# OakyWing-v0_1.net
KiCad netlist of a schematic drawn in EAGLE
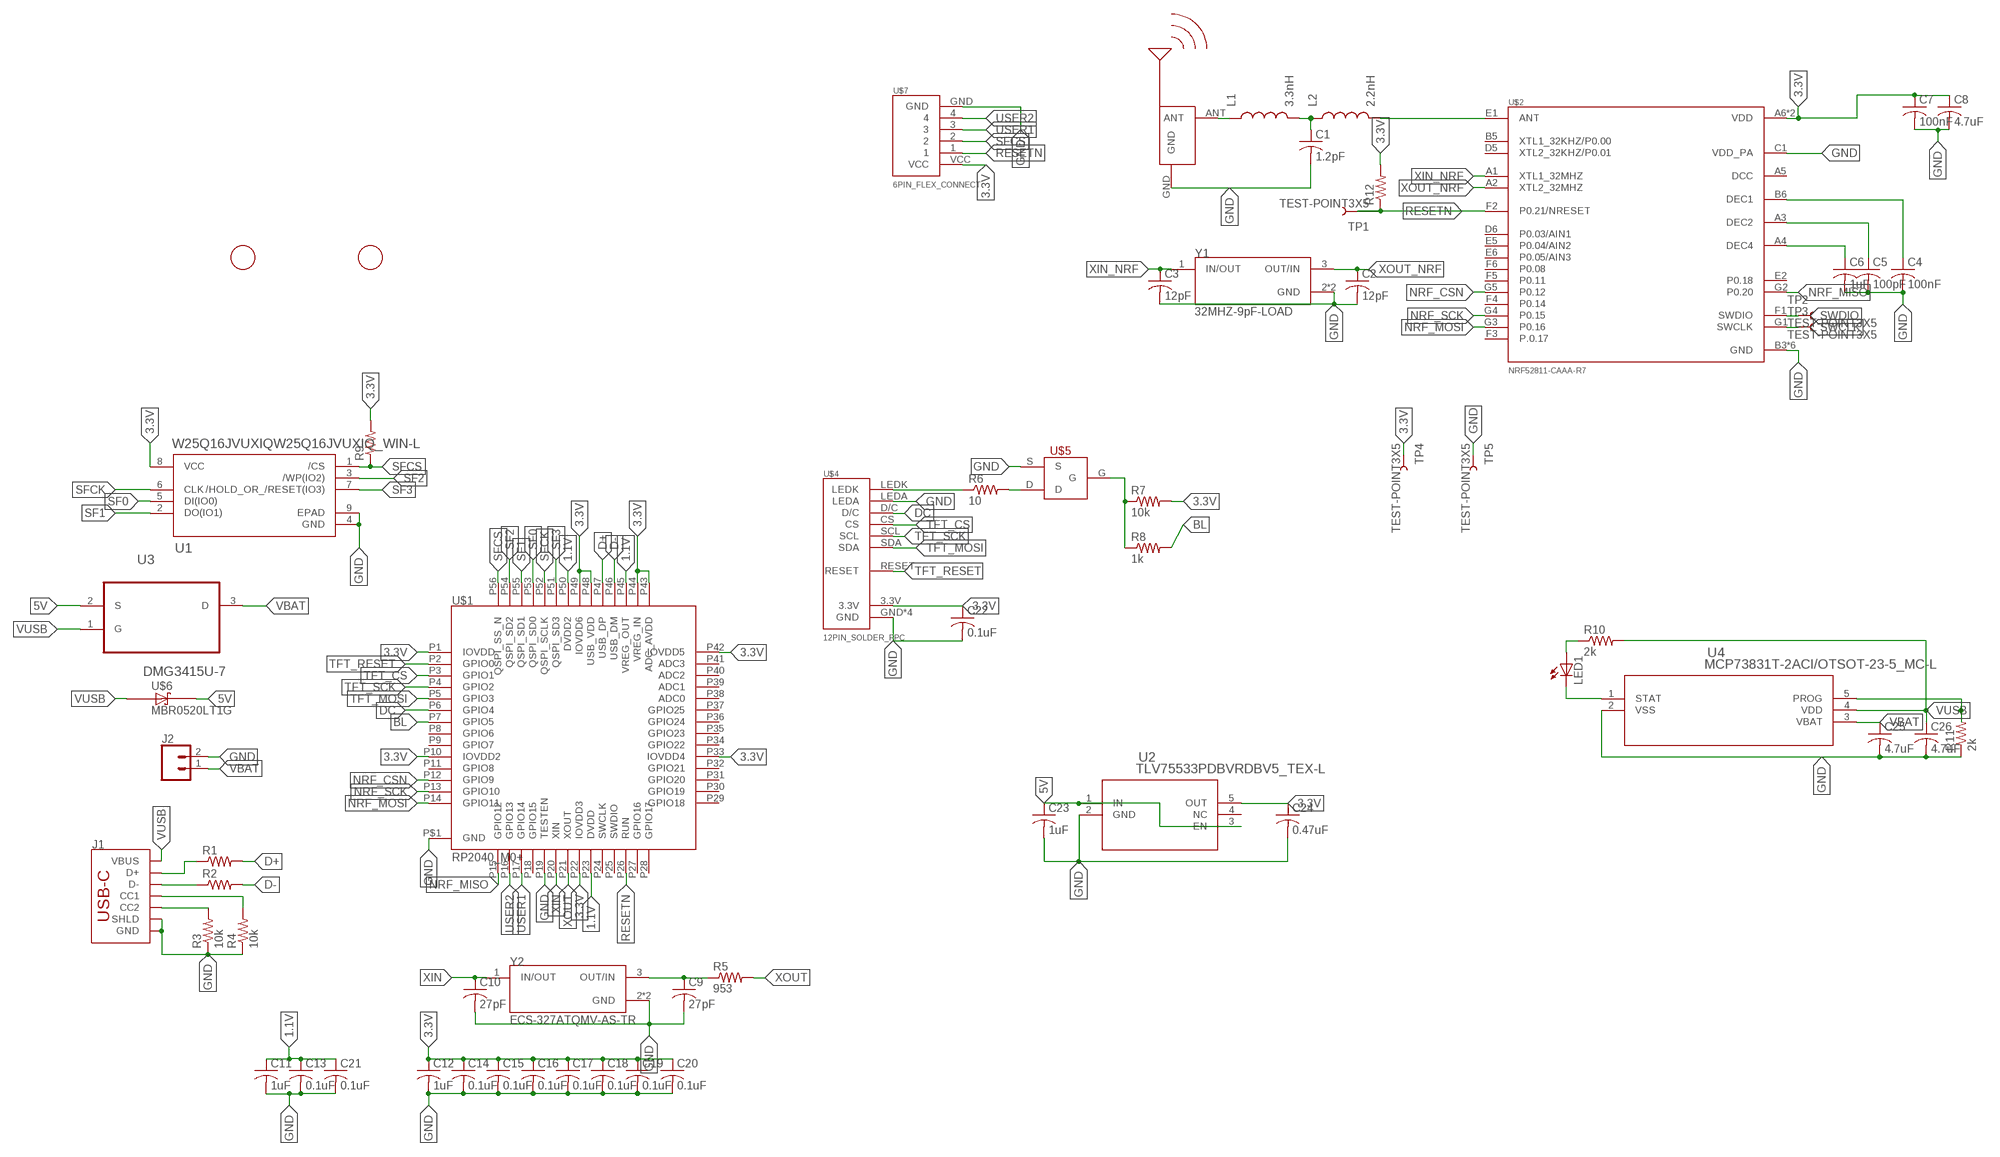
[diagram p0: schematic, sheet 1]

(export (version "E")
  (design (tool "Eeschema 10.0.6"))
  (components
    (comp (ref "C1")
      (value "1.2pF")
      (footprint "eagle-import:C0402")
      (libsource (lib "eagle-import") (part "rcl_334_C-USC0402"))
    )
    (comp (ref "C2")
      (value "12pF")
      (footprint "eagle-import:C0402")
      (libsource (lib "eagle-import") (part "rcl_334_C-USC0402"))
    )
    (comp (ref "C3")
      (value "12pF")
      (footprint "eagle-import:C0402")
      (libsource (lib "eagle-import") (part "C-USC0402"))
    )
    (comp (ref "C4")
      (value "100nF")
      (footprint "eagle-import:C0402")
      (libsource (lib "eagle-import") (part "rcl_334_C-USC0402"))
    )
    (comp (ref "C5")
      (value "100pF")
      (footprint "eagle-import:C0402")
      (libsource (lib "eagle-import") (part "rcl_334_C-USC0402"))
    )
    (comp (ref "C6")
      (value "1uF")
      (footprint "eagle-import:C0402")
      (libsource (lib "eagle-import") (part "rcl_334_C-USC0402"))
    )
    (comp (ref "C7")
      (value "100nF")
      (footprint "eagle-import:C0402")
      (libsource (lib "eagle-import") (part "rcl_334_C-USC0402"))
    )
    (comp (ref "C8")
      (value "4.7uF")
      (footprint "eagle-import:C0603")
      (libsource (lib "eagle-import") (part "rcl_334_C-USC0603"))
    )
    (comp (ref "C9")
      (value "27pF")
      (footprint "eagle-import:C0402")
      (libsource (lib "eagle-import") (part "C-USC0402"))
    )
    (comp (ref "C10")
      (value "27pF")
      (footprint "eagle-import:C0402")
      (libsource (lib "eagle-import") (part "C-USC0402"))
    )
    (comp (ref "C11")
      (value "1uF")
      (footprint "eagle-import:C0402")
      (libsource (lib "eagle-import") (part "C-USC0402"))
    )
    (comp (ref "C12")
      (value "1uF")
      (footprint "eagle-import:C0402")
      (libsource (lib "eagle-import") (part "C-USC0402"))
    )
    (comp (ref "C13")
      (value "0.1uF")
      (footprint "eagle-import:C0402")
      (libsource (lib "eagle-import") (part "C-USC0402"))
    )
    (comp (ref "C14")
      (value "0.1uF")
      (footprint "eagle-import:C0402")
      (libsource (lib "eagle-import") (part "C-USC0402"))
    )
    (comp (ref "C15")
      (value "0.1uF")
      (footprint "eagle-import:C0402")
      (libsource (lib "eagle-import") (part "C-USC0402"))
    )
    (comp (ref "C16")
      (value "0.1uF")
      (footprint "eagle-import:C0402")
      (libsource (lib "eagle-import") (part "C-USC0402"))
    )
    (comp (ref "C17")
      (value "0.1uF")
      (footprint "eagle-import:C0402")
      (libsource (lib "eagle-import") (part "C-USC0402"))
    )
    (comp (ref "C18")
      (value "0.1uF")
      (footprint "eagle-import:C0402")
      (libsource (lib "eagle-import") (part "C-USC0402"))
    )
    (comp (ref "C19")
      (value "0.1uF")
      (footprint "eagle-import:C0402")
      (libsource (lib "eagle-import") (part "C-USC0402"))
    )
    (comp (ref "C20")
      (value "0.1uF")
      (footprint "eagle-import:C0402")
      (libsource (lib "eagle-import") (part "C-USC0402"))
    )
    (comp (ref "C21")
      (value "0.1uF")
      (footprint "eagle-import:C0402")
      (libsource (lib "eagle-import") (part "C-USC0402"))
    )
    (comp (ref "C22")
      (value "0.1uF")
      (footprint "eagle-import:C0402")
      (libsource (lib "eagle-import") (part "rcl_334_C-USC0402"))
    )
    (comp (ref "C23")
      (value "1uF")
      (footprint "eagle-import:C0402")
      (libsource (lib "eagle-import") (part "rcl_334_C-USC0402"))
    )
    (comp (ref "C24")
      (value "0.47uF")
      (footprint "eagle-import:C0402")
      (libsource (lib "eagle-import") (part "rcl_334_C-USC0402"))
    )
    (comp (ref "C25")
      (value "4.7uF")
      (footprint "eagle-import:C0603")
      (libsource (lib "eagle-import") (part "rcl_334_C-USC0603"))
    )
    (comp (ref "C26")
      (value "4.7uF")
      (footprint "eagle-import:C0603")
      (libsource (lib "eagle-import") (part "rcl_334_C-USC0603"))
    )
    (comp (ref "J1")
      (value "USB_C_2-LAYER_PADS")
      (footprint "eagle-import:USB-C-16P-2LAYER-PADS")
      (libsource (lib "eagle-import") (part "USB_C_2-LAYER_PADS"))
    )
    (comp (ref "J2")
      (value "CONN_02")
      (footprint "eagle-import:1X02")
      (libsource (lib "eagle-import") (part "CONN_02"))
    )
    (comp (ref "L1")
      (value "3.3nH")
      (footprint "eagle-import:R0402")
      (libsource (lib "eagle-import") (part "INDUCTOR"))
    )
    (comp (ref "L2")
      (value "2.2nH")
      (footprint "eagle-import:R0402")
      (libsource (lib "eagle-import") (part "INDUCTOR"))
    )
    (comp (ref "LED1")
      (value "LEDCHIP-LED0603")
      (footprint "eagle-import:CHIP-LED0603")
      (libsource (lib "eagle-import") (part "LEDCHIP-LED0603"))
    )
    (comp (ref "R1")
      (value "R-US_R0603")
      (footprint "eagle-import:R0603")
      (libsource (lib "eagle-import") (part "rcl_334_R-US_R0603"))
    )
    (comp (ref "R2")
      (value "R-US_R0603")
      (footprint "eagle-import:R0603")
      (libsource (lib "eagle-import") (part "rcl_334_R-US_R0603"))
    )
    (comp (ref "R3")
      (value "10k")
      (footprint "eagle-import:R0402")
      (libsource (lib "eagle-import") (part "R-US_R0402"))
    )
    (comp (ref "R4")
      (value "10k")
      (footprint "eagle-import:R0402")
      (libsource (lib "eagle-import") (part "R-US_R0402"))
    )
    (comp (ref "R5")
      (value "953")
      (footprint "eagle-import:R0402")
      (libsource (lib "eagle-import") (part "R-US_R0402"))
    )
    (comp (ref "R6")
      (value "10")
      (footprint "eagle-import:R0402")
      (libsource (lib "eagle-import") (part "rcl_334_R-US_R0402"))
    )
    (comp (ref "R7")
      (value "10k")
      (footprint "eagle-import:R0402")
      (libsource (lib "eagle-import") (part "rcl_334_R-US_R0402"))
    )
    (comp (ref "R8")
      (value "1k")
      (footprint "eagle-import:R0402")
      (libsource (lib "eagle-import") (part "rcl_334_R-US_R0402"))
    )
    (comp (ref "R9")
      (value "R-US_R0402")
      (footprint "eagle-import:R0402")
      (libsource (lib "eagle-import") (part "rcl_334_R-US_R0402"))
    )
    (comp (ref "R10")
      (value "2k")
      (footprint "eagle-import:R0603")
      (libsource (lib "eagle-import") (part "rcl_334_R-US_R0603"))
    )
    (comp (ref "R11")
      (value "2k")
      (footprint "eagle-import:R0603")
      (libsource (lib "eagle-import") (part "rcl_334_R-US_R0603"))
    )
    (comp (ref "R12")
      (value "R-US_R0402")
      (footprint "eagle-import:R0402")
      (libsource (lib "eagle-import") (part "rcl_334_R-US_R0402"))
    )
    (comp (ref "TP1")
      (value "TEST-POINT3X5")
      (footprint "eagle-import:PAD.03X.05")
      (libsource (lib "eagle-import") (part "TEST-POINT3X5"))
    )
    (comp (ref "TP2")
      (value "TEST-POINT3X5")
      (footprint "eagle-import:PAD.03X.05")
      (libsource (lib "eagle-import") (part "TEST-POINT3X5"))
    )
    (comp (ref "TP3")
      (value "TEST-POINT3X5")
      (footprint "eagle-import:PAD.03X.05")
      (libsource (lib "eagle-import") (part "TEST-POINT3X5"))
    )
    (comp (ref "TP4")
      (value "TEST-POINT3X5")
      (footprint "eagle-import:PAD.03X.05")
      (libsource (lib "eagle-import") (part "TEST-POINT3X5"))
    )
    (comp (ref "TP5")
      (value "TEST-POINT3X5")
      (footprint "eagle-import:PAD.03X.05")
      (libsource (lib "eagle-import") (part "TEST-POINT3X5"))
    )
    (comp (ref "U$1")
      (value "RP2040_M0+")
      (footprint "eagle-import:QFN-56")
      (libsource (lib "eagle-import") (part "RP2040_M0+"))
    )
    (comp (ref "U$2")
      (value "NRF52811-CAAA-R7")
      (footprint "eagle-import:WLCSP")
      (libsource (lib "eagle-import") (part "NRF52811-CAAA-R7"))
    )
    (comp (ref "U$3")
      (value "BLE-2.45GHZ-ANTBLE-2.45GHZ-SERP-ANT")
      (footprint "eagle-import:2.45GHZ-SERPENTINE")
      (libsource (lib "eagle-import") (part "BLE-2.45GHZ-ANTBLE-2.45GHZ-SERP-ANT"))
    )
    (comp (ref "U$4")
      (value "12PIN_SOLDER_FPC")
      (footprint "eagle-import:12PIN_SOLDER_FPC")
      (libsource (lib "eagle-import") (part "12PIN_SOLDER_FPC"))
    )
    (comp (ref "U$5")
      (value "DMN65D8L-7")
      (footprint "eagle-import:SOT-23")
      (libsource (lib "eagle-import") (part "DMN65D8L-7"))
    )
    (comp (ref "U$6")
      (value "MBR0520LT1G")
      (footprint "eagle-import:SOD3716X117(SOD-123)")
      (fields (field (name "MF") "ON Semiconductor"))
      (libsource (lib "eagle-import") (part "MBR0520LT1G"))
    )
    (comp (ref "U$7")
      (value "6PIN_FLEX_CONNECT")
      (footprint "eagle-import:6PIN_0.7MM")
      (libsource (lib "eagle-import") (part "6PIN_FLEX_CONNECT"))
    )
    (comp (ref "U$8")
      (value "FIDUCIAL")
      (footprint "eagle-import:FIDUCIAL_1MM")
      (libsource (lib "eagle-import") (part "FIDUCIAL"))
    )
    (comp (ref "U$9")
      (value "FIDUCIAL")
      (footprint "eagle-import:FIDUCIAL_1MM")
      (libsource (lib "eagle-import") (part "FIDUCIAL"))
    )
    (comp (ref "U1")
      (value "W25Q16JVUXIQW25Q16JVUXIQ_WIN-L")
      (footprint "eagle-import:W25Q16JVUXIQ_WIN-L")
      (fields
        (field (name "MANUFACTURER_PART_NUMBER") "W25Q16JVUXIQ")
        (field (name "COPYRIGHT") "Copyright (C) 2018 Accelerated Designs. All rights reserved")
      )
      (libsource (lib "eagle-import") (part "W25Q16JVUXIQW25Q16JVUXIQ_WIN-L"))
    )
    (comp (ref "U2")
      (value "TLV75533PDBVRDBV5_TEX-L")
      (footprint "eagle-import:DBV5_TEX-L")
      (fields
        (field (name "MANUFACTURER_PART_NUMBER") "TLV75533PDBVR")
        (field (name "COPYRIGHT") "Copyright (C) 2018 Accelerated Designs. All rights reserved")
      )
      (libsource (lib "eagle-import") (part "TLV75533PDBVRDBV5_TEX-L"))
    )
    (comp (ref "U3")
      (value "DMG3415U-7")
      (footprint "eagle-import:SOT95P240X105-3N")
      (fields (field (name "MF") "Diodes Inc."))
      (libsource (lib "eagle-import") (part "DMG3415U-7"))
    )
    (comp (ref "U4")
      (value "MCP73831T-2ACI/OTSOT-23-5_MC-L")
      (footprint "eagle-import:SOT-23-5_MC-L")
      (fields (field (name "MANUFACTURER_PART_NUMBER") "MCP73831T-2ACI/OT"))
      (libsource (lib "eagle-import") (part "MCP73831T-2ACI/OTSOT-23-5_MC-L"))
    )
    (comp (ref "Y1")
      (value "32MHZ-9pF-LOAD")
      (footprint "eagle-import:XTAL_ECS-327ATQMV-AS-TR")
      (fields
        (field (name "DIGI-KEY_PART_NUMBER") "XC2826CT-ND")
        (field (name "MF") "ECS Inc.")
        (field (name "MP") "ECS-327ATQMV-AS-TR")
      )
      (libsource (lib "eagle-import") (part "ECS-327ATQMV-AS-TR"))
    )
    (comp (ref "Y2")
      (value "ECS-327ATQMV-AS-TR")
      (footprint "eagle-import:XTAL_ECS-327ATQMV-AS-TR")
      (fields (field (name "DIGI-KEY_PART_NUMBER") "XC2826CT-ND") (field (name "MF") "ECS Inc."))
      (libsource (lib "eagle-import") (part "ECS-327ATQMV-AS-TR"))
    )
  )
  (nets
    (net (code "1") (name "1.1V") (class "Default")
      (node (ref "C11") (pin "1") (pinfunction "1_1") (pintype "passive"))
      (node (ref "C13") (pin "1") (pinfunction "1_1") (pintype "passive"))
      (node (ref "C21") (pin "1") (pinfunction "1_1") (pintype "passive"))
      (node (ref "U$1") (pin "P23") (pinfunction "DVDD_P23") (pintype "bidirectional"))
      (node (ref "U$1") (pin "P45") (pinfunction "VREG_OUT_P45") (pintype "bidirectional"))
      (node (ref "U$1") (pin "P50") (pinfunction "DVDD2_P50") (pintype "bidirectional"))
    )
    (net (code "2") (name "3.3V") (class "Default")
      (node (ref "C12") (pin "1") (pinfunction "1_1") (pintype "passive"))
      (node (ref "C14") (pin "1") (pinfunction "1_1") (pintype "passive"))
      (node (ref "C15") (pin "1") (pinfunction "1_1") (pintype "passive"))
      (node (ref "C16") (pin "1") (pinfunction "1_1") (pintype "passive"))
      (node (ref "C17") (pin "1") (pinfunction "1_1") (pintype "passive"))
      (node (ref "C18") (pin "1") (pinfunction "1_1") (pintype "passive"))
      (node (ref "C19") (pin "1") (pinfunction "1_1") (pintype "passive"))
      (node (ref "C20") (pin "1") (pinfunction "1_1") (pintype "passive"))
      (node (ref "C22") (pin "1") (pinfunction "1_1") (pintype "passive"))
      (node (ref "C24") (pin "1") (pinfunction "1_1") (pintype "passive"))
      (node (ref "C7") (pin "1") (pinfunction "1_1") (pintype "passive"))
      (node (ref "C8") (pin "1") (pinfunction "1_1") (pintype "passive"))
      (node (ref "R12") (pin "2") (pinfunction "2_2") (pintype "passive"))
      (node (ref "R7") (pin "2") (pinfunction "2_2") (pintype "passive"))
      (node (ref "R9") (pin "2") (pinfunction "2_2") (pintype "passive"))
      (node (ref "TP4") (pin "P$1") (pinfunction "1_P$1") (pintype "bidirectional"))
      (node (ref "U$1") (pin "P1") (pinfunction "IOVDD_P1") (pintype "bidirectional"))
      (node (ref "U$1") (pin "P10") (pinfunction "IOVDD2_P10") (pintype "bidirectional"))
      (node (ref "U$1") (pin "P22") (pinfunction "IOVDD3_P22") (pintype "bidirectional"))
      (node (ref "U$1") (pin "P33") (pinfunction "IOVDD4_P33") (pintype "bidirectional"))
      (node (ref "U$1") (pin "P42") (pinfunction "IOVDD5_P42") (pintype "bidirectional"))
      (node (ref "U$1") (pin "P43") (pinfunction "ADC_AVDD_P43") (pintype "bidirectional"))
      (node (ref "U$1") (pin "P44") (pinfunction "VREG_IN_P44") (pintype "bidirectional"))
      (node (ref "U$1") (pin "P48") (pinfunction "USB_VDD_P48") (pintype "bidirectional"))
      (node (ref "U$1") (pin "P49") (pinfunction "IOVDD6_P49") (pintype "bidirectional"))
      (node (ref "U$2") (pin "A6") (pinfunction "VDD_A6") (pintype "bidirectional"))
      (node (ref "U$2") (pin "G6") (pinfunction "VDD_G6") (pintype "bidirectional"))
      (node (ref "U$4") (pin "3.3V") (pinfunction "3.3V_3.3V") (pintype "bidirectional"))
      (node (ref "U$7") (pin "VCC") (pinfunction "VCC_VCC") (pintype "bidirectional"))
      (node (ref "U1") (pin "8") (pinfunction "VCC_8") (pintype "passive"))
      (node (ref "U2") (pin "5") (pinfunction "OUT_5") (pintype "output"))
    )
    (net (code "3") (name "5V") (class "Default")
      (node (ref "C23") (pin "1") (pinfunction "1_1") (pintype "passive"))
      (node (ref "U$6") (pin "1") (pinfunction "C_1") (pintype "passive"))
      (node (ref "U2") (pin "1") (pinfunction "IN_1") (pintype "input"))
      (node (ref "U2") (pin "3") (pinfunction "EN_3") (pintype "input"))
      (node (ref "U3") (pin "2") (pinfunction "S_2") (pintype "passive"))
    )
    (net (code "4") (name "BL") (class "Default")
      (node (ref "R8") (pin "2") (pinfunction "2_2") (pintype "passive"))
      (node (ref "U$1") (pin "P7") (pinfunction "GPIO5_P7") (pintype "bidirectional"))
    )
    (net (code "5") (name "D+") (class "Default")
      (node (ref "R1") (pin "2") (pinfunction "2_2") (pintype "passive"))
      (node (ref "U$1") (pin "P47") (pinfunction "USB_DP_P47") (pintype "bidirectional"))
    )
    (net (code "6") (name "D-") (class "Default")
      (node (ref "R2") (pin "2") (pinfunction "2_2") (pintype "passive"))
      (node (ref "U$1") (pin "P46") (pinfunction "USB_DM_P46") (pintype "bidirectional"))
    )
    (net (code "7") (name "DC") (class "Default")
      (node (ref "U$1") (pin "P6") (pinfunction "GPIO4_P6") (pintype "bidirectional"))
      (node (ref "U$4") (pin "D/C") (pinfunction "D/C_D/C") (pintype "bidirectional"))
    )
    (net (code "8") (name "GND") (class "Default")
      (node (ref "C1") (pin "2") (pinfunction "2_2") (pintype "passive"))
      (node (ref "C10") (pin "2") (pinfunction "2_2") (pintype "passive"))
      (node (ref "C11") (pin "2") (pinfunction "2_2") (pintype "passive"))
      (node (ref "C12") (pin "2") (pinfunction "2_2") (pintype "passive"))
      (node (ref "C13") (pin "2") (pinfunction "2_2") (pintype "passive"))
      (node (ref "C14") (pin "2") (pinfunction "2_2") (pintype "passive"))
      (node (ref "C15") (pin "2") (pinfunction "2_2") (pintype "passive"))
      (node (ref "C16") (pin "2") (pinfunction "2_2") (pintype "passive"))
      (node (ref "C17") (pin "2") (pinfunction "2_2") (pintype "passive"))
      (node (ref "C18") (pin "2") (pinfunction "2_2") (pintype "passive"))
      (node (ref "C19") (pin "2") (pinfunction "2_2") (pintype "passive"))
      (node (ref "C2") (pin "2") (pinfunction "2_2") (pintype "passive"))
      (node (ref "C20") (pin "2") (pinfunction "2_2") (pintype "passive"))
      (node (ref "C21") (pin "2") (pinfunction "2_2") (pintype "passive"))
      (node (ref "C22") (pin "2") (pinfunction "2_2") (pintype "passive"))
      (node (ref "C23") (pin "2") (pinfunction "2_2") (pintype "passive"))
      (node (ref "C24") (pin "2") (pinfunction "2_2") (pintype "passive"))
      (node (ref "C25") (pin "2") (pinfunction "2_2") (pintype "passive"))
      (node (ref "C26") (pin "2") (pinfunction "2_2") (pintype "passive"))
      (node (ref "C3") (pin "2") (pinfunction "2_2") (pintype "passive"))
      (node (ref "C4") (pin "2") (pinfunction "2_2") (pintype "passive"))
      (node (ref "C5") (pin "2") (pinfunction "2_2") (pintype "passive"))
      (node (ref "C6") (pin "2") (pinfunction "2_2") (pintype "passive"))
      (node (ref "C7") (pin "2") (pinfunction "2_2") (pintype "passive"))
      (node (ref "C8") (pin "2") (pinfunction "2_2") (pintype "passive"))
      (node (ref "C9") (pin "2") (pinfunction "2_2") (pintype "passive"))
      (node (ref "J1") (pin "GND") (pinfunction "GND_GND") (pintype "bidirectional"))
      (node (ref "J1") (pin "GND2") (pinfunction "GND_GND2") (pintype "bidirectional"))
      (node (ref "J1") (pin "P$1") (pinfunction "SHLD_P$1") (pintype "bidirectional"))
      (node (ref "J1") (pin "P$2") (pinfunction "SHLD_P$2") (pintype "bidirectional"))
      (node (ref "J1") (pin "P$3") (pinfunction "SHLD_P$3") (pintype "bidirectional"))
      (node (ref "J1") (pin "P$4") (pinfunction "SHLD_P$4") (pintype "bidirectional"))
      (node (ref "J1") (pin "SHLD1") (pinfunction "SHLD_SHLD1") (pintype "bidirectional"))
      (node (ref "J1") (pin "SHLD2") (pinfunction "SHLD_SHLD2") (pintype "bidirectional"))
      (node (ref "J1") (pin "SHLD3") (pinfunction "SHLD_SHLD3") (pintype "bidirectional"))
      (node (ref "J1") (pin "SHLD4") (pinfunction "SHLD_SHLD4") (pintype "bidirectional"))
      (node (ref "J2") (pin "2") (pinfunction "2_2") (pintype "passive"))
      (node (ref "R11") (pin "1") (pinfunction "1_1") (pintype "passive"))
      (node (ref "R3") (pin "1") (pinfunction "1_1") (pintype "passive"))
      (node (ref "R4") (pin "1") (pinfunction "1_1") (pintype "passive"))
      (node (ref "TP5") (pin "P$1") (pinfunction "1_P$1") (pintype "bidirectional"))
      (node (ref "U$1") (pin "P$1") (pinfunction "GND_P$1") (pintype "bidirectional"))
      (node (ref "U$1") (pin "P19") (pinfunction "TESTEN_P19") (pintype "bidirectional"))
      (node (ref "U$2") (pin "B3") (pinfunction "GND_B3") (pintype "bidirectional"))
      (node (ref "U$2") (pin "B4") (pinfunction "GND_B4") (pintype "bidirectional"))
      (node (ref "U$2") (pin "C1") (pinfunction "VDD_PA_C1") (pintype "bidirectional"))
      (node (ref "U$2") (pin "D3") (pinfunction "GND_D3") (pintype "bidirectional"))
      (node (ref "U$2") (pin "D4") (pinfunction "GND_D4") (pintype "bidirectional"))
      (node (ref "U$2") (pin "E3") (pinfunction "GND_E3") (pintype "bidirectional"))
      (node (ref "U$2") (pin "E4") (pinfunction "GND_E4") (pintype "bidirectional"))
      (node (ref "U$3") (pin "GND") (pinfunction "GND_GND") (pintype "bidirectional"))
      (node (ref "U$4") (pin "GND") (pinfunction "GND_GND") (pintype "bidirectional"))
      (node (ref "U$4") (pin "GND2") (pinfunction "GND_GND2") (pintype "bidirectional"))
      (node (ref "U$4") (pin "GND3") (pinfunction "GND_GND3") (pintype "bidirectional"))
      (node (ref "U$4") (pin "GND4") (pinfunction "GND_GND4") (pintype "bidirectional"))
      (node (ref "U$4") (pin "LEDA") (pinfunction "LEDA_LEDA") (pintype "bidirectional"))
      (node (ref "U$5") (pin "S") (pinfunction "S_S") (pintype "bidirectional"))
      (node (ref "U$7") (pin "GND") (pinfunction "GND_GND") (pintype "bidirectional"))
      (node (ref "U1") (pin "4") (pinfunction "GND_4") (pintype "passive"))
      (node (ref "U1") (pin "9") (pinfunction "EPAD_9") (pintype "passive"))
      (node (ref "U2") (pin "2") (pinfunction "GND_2") (pintype "power_in"))
      (node (ref "U4") (pin "2") (pinfunction "VSS_2") (pintype "passive"))
      (node (ref "Y1") (pin "2") (pinfunction "GND_2") (pintype "power_in"))
      (node (ref "Y1") (pin "4") (pinfunction "GND_4") (pintype "power_in"))
      (node (ref "Y2") (pin "2") (pinfunction "GND_2") (pintype "power_in"))
      (node (ref "Y2") (pin "4") (pinfunction "GND_4") (pintype "power_in"))
    )
    (net (code "9") (name "NRF_CSN") (class "Default")
      (node (ref "U$1") (pin "P12") (pinfunction "GPIO9_P12") (pintype "bidirectional"))
      (node (ref "U$2") (pin "G5") (pinfunction "P0.12_G5") (pintype "bidirectional"))
    )
    (net (code "10") (name "NRF_MISO") (class "Default")
      (node (ref "U$1") (pin "P15") (pinfunction "GPIO12_P15") (pintype "bidirectional"))
      (node (ref "U$2") (pin "G2") (pinfunction "P0.20_G2") (pintype "bidirectional"))
    )
    (net (code "11") (name "NRF_MOSI") (class "Default")
      (node (ref "U$1") (pin "P14") (pinfunction "GPIO11_P14") (pintype "bidirectional"))
      (node (ref "U$2") (pin "G3") (pinfunction "P0.16_G3") (pintype "bidirectional"))
    )
    (net (code "12") (name "NRF_SCK") (class "Default")
      (node (ref "U$1") (pin "P13") (pinfunction "GPIO10_P13") (pintype "bidirectional"))
      (node (ref "U$2") (pin "G4") (pinfunction "P0.15_G4") (pintype "bidirectional"))
    )
    (net (code "13") (name "Net-(C1-Pad1)") (class "Default")
      (node (ref "C1") (pin "1") (pinfunction "1_1") (pintype "passive"))
      (node (ref "L1") (pin "2") (pinfunction "2_2") (pintype "passive"))
      (node (ref "L2") (pin "1") (pinfunction "1_1") (pintype "passive"))
    )
    (net (code "14") (name "Net-(J1-CC1)") (class "Default")
      (node (ref "J1") (pin "A5") (pinfunction "CC1_A5") (pintype "bidirectional"))
      (node (ref "R4") (pin "2") (pinfunction "2_2") (pintype "passive"))
    )
    (net (code "15") (name "Net-(J1-CC2)") (class "Default")
      (node (ref "J1") (pin "B5") (pinfunction "CC2_B5") (pintype "bidirectional"))
      (node (ref "R3") (pin "2") (pinfunction "2_2") (pintype "passive"))
    )
    (net (code "16") (name "Net-(J1-D+-PadA6)") (class "Default")
      (node (ref "J1") (pin "A6") (pinfunction "D+_A6") (pintype "bidirectional"))
      (node (ref "J1") (pin "B6") (pinfunction "D+_B6") (pintype "bidirectional"))
      (node (ref "R1") (pin "1") (pinfunction "1_1") (pintype "passive"))
    )
    (net (code "17") (name "Net-(J1-D--PadA7)") (class "Default")
      (node (ref "J1") (pin "A7") (pinfunction "D-_A7") (pintype "bidirectional"))
      (node (ref "J1") (pin "B7") (pinfunction "D-_B7") (pintype "bidirectional"))
      (node (ref "R2") (pin "1") (pinfunction "1_1") (pintype "passive"))
    )
    (net (code "18") (name "Net-(L1-Pad1)") (class "Default")
      (node (ref "L1") (pin "1") (pinfunction "1_1") (pintype "passive"))
      (node (ref "U$3") (pin "ANT") (pinfunction "ANT_ANT") (pintype "bidirectional"))
    )
    (net (code "19") (name "Net-(LED1-PadA)") (class "Default")
      (node (ref "LED1") (pin "A") (pinfunction "A_A") (pintype "passive"))
      (node (ref "R10") (pin "1") (pinfunction "1_1") (pintype "passive"))
    )
    (net (code "20") (name "Net-(R6-Pad1)") (class "Default")
      (node (ref "R6") (pin "1") (pinfunction "1_1") (pintype "passive"))
      (node (ref "U$4") (pin "LEDK") (pinfunction "LEDK_LEDK") (pintype "bidirectional"))
    )
    (net (code "21") (name "Net-(R6-Pad2)") (class "Default")
      (node (ref "R6") (pin "2") (pinfunction "2_2") (pintype "passive"))
      (node (ref "U$5") (pin "D") (pinfunction "D_D") (pintype "bidirectional"))
    )
    (net (code "22") (name "Net-(R7-Pad1)") (class "Default")
      (node (ref "R7") (pin "1") (pinfunction "1_1") (pintype "passive"))
      (node (ref "R8") (pin "1") (pinfunction "1_1") (pintype "passive"))
      (node (ref "U$5") (pin "G") (pinfunction "G_G") (pintype "bidirectional"))
    )
    (net (code "23") (name "Net-(U$2-ANT)") (class "Default")
      (node (ref "L2") (pin "2") (pinfunction "2_2") (pintype "passive"))
      (node (ref "U$2") (pin "E1") (pinfunction "ANT_E1") (pintype "bidirectional"))
    )
    (net (code "24") (name "Net-(U$2-DEC1)") (class "Default")
      (node (ref "C4") (pin "1") (pinfunction "1_1") (pintype "passive"))
      (node (ref "U$2") (pin "B6") (pinfunction "DEC1_B6") (pintype "bidirectional"))
    )
    (net (code "25") (name "Net-(U$2-DEC2)") (class "Default")
      (node (ref "C5") (pin "1") (pinfunction "1_1") (pintype "passive"))
      (node (ref "U$2") (pin "A3") (pinfunction "DEC2_A3") (pintype "bidirectional"))
    )
    (net (code "26") (name "Net-(U$2-DEC4)") (class "Default")
      (node (ref "C6") (pin "1") (pinfunction "1_1") (pintype "passive"))
      (node (ref "U$2") (pin "A4") (pinfunction "DEC4_A4") (pintype "bidirectional"))
    )
    (net (code "27") (name "Net-(U4-PROG)") (class "Default")
      (node (ref "R11") (pin "2") (pinfunction "2_2") (pintype "passive"))
      (node (ref "U4") (pin "5") (pinfunction "PROG_5") (pintype "passive"))
    )
    (net (code "28") (name "Net-(U4-STAT)") (class "Default")
      (node (ref "LED1") (pin "C") (pinfunction "C_C") (pintype "passive"))
      (node (ref "U4") (pin "1") (pinfunction "STAT_1") (pintype "passive"))
    )
    (net (code "29") (name "Net-(Y2-OUT{slash}IN)") (class "Default")
      (node (ref "C9") (pin "1") (pinfunction "1_1") (pintype "passive"))
      (node (ref "R5") (pin "1") (pinfunction "1_1") (pintype "passive"))
      (node (ref "Y2") (pin "3") (pinfunction "OUT/IN_3") (pintype "bidirectional"))
    )
    (net (code "30") (name "RESETN") (class "Default")
      (node (ref "R12") (pin "1") (pinfunction "1_1") (pintype "passive"))
      (node (ref "TP1") (pin "P$1") (pinfunction "1_P$1") (pintype "bidirectional"))
      (node (ref "U$1") (pin "P26") (pinfunction "RUN_P26") (pintype "bidirectional"))
      (node (ref "U$2") (pin "F2") (pinfunction "P0.21/NRESET_F2") (pintype "bidirectional"))
      (node (ref "U$7") (pin "1") (pinfunction "1_1") (pintype "bidirectional"))
    )
    (net (code "31") (name "SF0") (class "Default")
      (node (ref "U$1") (pin "P53") (pinfunction "QSPI_SD0_P53") (pintype "bidirectional"))
      (node (ref "U1") (pin "5") (pinfunction "DI(IO0)_5") (pintype "passive"))
    )
    (net (code "32") (name "SF1") (class "Default")
      (node (ref "U$1") (pin "P55") (pinfunction "QSPI_SD1_P55") (pintype "bidirectional"))
      (node (ref "U1") (pin "2") (pinfunction "DO(IO1)_2") (pintype "passive"))
    )
    (net (code "33") (name "SF2") (class "Default")
      (node (ref "U$1") (pin "P54") (pinfunction "QSPI_SD2_P54") (pintype "bidirectional"))
      (node (ref "U1") (pin "3") (pinfunction "/WP(IO2)_3") (pintype "passive"))
    )
    (net (code "34") (name "SF3") (class "Default")
      (node (ref "U$1") (pin "P51") (pinfunction "QSPI_SD3_P51") (pintype "bidirectional"))
      (node (ref "U1") (pin "7") (pinfunction "/HOLD_OR_/RESET(IO3)_7") (pintype "passive"))
    )
    (net (code "35") (name "SFCK") (class "Default")
      (node (ref "U$1") (pin "P52") (pinfunction "QSPI_SCLK_P52") (pintype "bidirectional"))
      (node (ref "U1") (pin "6") (pinfunction "CLK_6") (pintype "passive"))
    )
    (net (code "36") (name "SFCS") (class "Default")
      (node (ref "R9") (pin "1") (pinfunction "1_1") (pintype "passive"))
      (node (ref "U$1") (pin "P56") (pinfunction "QSPI_SS_N_P56") (pintype "bidirectional"))
      (node (ref "U$7") (pin "2") (pinfunction "2_2") (pintype "bidirectional"))
      (node (ref "U1") (pin "1") (pinfunction "/CS_1") (pintype "passive"))
    )
    (net (code "37") (name "SWCLK") (class "Default")
      (node (ref "TP3") (pin "P$1") (pinfunction "1_P$1") (pintype "bidirectional"))
      (node (ref "U$2") (pin "G1") (pinfunction "SWCLK_G1") (pintype "bidirectional"))
    )
    (net (code "38") (name "SWDIO") (class "Default")
      (node (ref "TP2") (pin "P$1") (pinfunction "1_P$1") (pintype "bidirectional"))
      (node (ref "U$2") (pin "F1") (pinfunction "SWDIO_F1") (pintype "bidirectional"))
    )
    (net (code "39") (name "TFT_CS") (class "Default")
      (node (ref "U$1") (pin "P3") (pinfunction "GPIO1_P3") (pintype "bidirectional"))
      (node (ref "U$4") (pin "CS") (pinfunction "CS_CS") (pintype "bidirectional"))
    )
    (net (code "40") (name "TFT_MOSI") (class "Default")
      (node (ref "U$1") (pin "P5") (pinfunction "GPIO3_P5") (pintype "bidirectional"))
      (node (ref "U$4") (pin "SDA") (pinfunction "SDA_SDA") (pintype "bidirectional"))
    )
    (net (code "41") (name "TFT_RESET") (class "Default")
      (node (ref "U$1") (pin "P2") (pinfunction "GPIO0_P2") (pintype "bidirectional"))
      (node (ref "U$4") (pin "RESET") (pinfunction "RESET_RESET") (pintype "bidirectional"))
    )
    (net (code "42") (name "TFT_SCK") (class "Default")
      (node (ref "U$1") (pin "P4") (pinfunction "GPIO2_P4") (pintype "bidirectional"))
      (node (ref "U$4") (pin "SCL") (pinfunction "SCL_SCL") (pintype "bidirectional"))
    )
    (net (code "43") (name "USER1") (class "Default")
      (node (ref "U$1") (pin "P17") (pinfunction "GPIO14_P17") (pintype "bidirectional"))
      (node (ref "U$7") (pin "3") (pinfunction "3_3") (pintype "bidirectional"))
    )
    (net (code "44") (name "USER2") (class "Default")
      (node (ref "U$1") (pin "P16") (pinfunction "GPIO13_P16") (pintype "bidirectional"))
      (node (ref "U$7") (pin "4") (pinfunction "4_4") (pintype "bidirectional"))
    )
    (net (code "45") (name "VBAT") (class "Default")
      (node (ref "C25") (pin "1") (pinfunction "1_1") (pintype "passive"))
      (node (ref "J2") (pin "1") (pinfunction "1_1") (pintype "passive"))
      (node (ref "U3") (pin "3") (pinfunction "D_3") (pintype "output"))
      (node (ref "U4") (pin "3") (pinfunction "VBAT_3") (pintype "passive"))
    )
    (net (code "46") (name "VUSB") (class "Default")
      (node (ref "C26") (pin "1") (pinfunction "1_1") (pintype "passive"))
      (node (ref "J1") (pin "VBUS1") (pinfunction "VBUS_VBUS1") (pintype "bidirectional"))
      (node (ref "J1") (pin "VBUS2") (pinfunction "VBUS_VBUS2") (pintype "bidirectional"))
      (node (ref "R10") (pin "2") (pinfunction "2_2") (pintype "passive"))
      (node (ref "U$6") (pin "2") (pinfunction "A_2") (pintype "passive"))
      (node (ref "U3") (pin "1") (pinfunction "G_1") (pintype "power_in"))
      (node (ref "U4") (pin "4") (pinfunction "VDD_4") (pintype "passive"))
    )
    (net (code "47") (name "XIN") (class "Default")
      (node (ref "C10") (pin "1") (pinfunction "1_1") (pintype "passive"))
      (node (ref "U$1") (pin "P20") (pinfunction "XIN_P20") (pintype "bidirectional"))
      (node (ref "Y2") (pin "1") (pinfunction "IN/OUT_1") (pintype "bidirectional"))
    )
    (net (code "48") (name "XIN_NRF") (class "Default")
      (node (ref "C3") (pin "1") (pinfunction "1_1") (pintype "passive"))
      (node (ref "U$2") (pin "A1") (pinfunction "XTL1_32MHZ_A1") (pintype "bidirectional"))
      (node (ref "Y1") (pin "1") (pinfunction "IN/OUT_1") (pintype "bidirectional"))
    )
    (net (code "49") (name "XOUT") (class "Default")
      (node (ref "R5") (pin "2") (pinfunction "2_2") (pintype "passive"))
      (node (ref "U$1") (pin "P21") (pinfunction "XOUT_P21") (pintype "bidirectional"))
    )
    (net (code "50") (name "XOUT_NRF") (class "Default")
      (node (ref "C2") (pin "1") (pinfunction "1_1") (pintype "passive"))
      (node (ref "U$2") (pin "A2") (pinfunction "XTL2_32MHZ_A2") (pintype "bidirectional"))
      (node (ref "Y1") (pin "3") (pinfunction "OUT/IN_3") (pintype "bidirectional"))
    )
    (net (code "51") (name "unconnected-(U$1-ADC0-PadP38)") (class "Default")
      (node (ref "U$1") (pin "P38") (pinfunction "ADC0_P38") (pintype "bidirectional"))
    )
    (net (code "52") (name "unconnected-(U$1-ADC1-PadP39)") (class "Default")
      (node (ref "U$1") (pin "P39") (pinfunction "ADC1_P39") (pintype "bidirectional"))
    )
    (net (code "53") (name "unconnected-(U$1-ADC2-PadP40)") (class "Default")
      (node (ref "U$1") (pin "P40") (pinfunction "ADC2_P40") (pintype "bidirectional"))
    )
    (net (code "54") (name "unconnected-(U$1-ADC3-PadP41)") (class "Default")
      (node (ref "U$1") (pin "P41") (pinfunction "ADC3_P41") (pintype "bidirectional"))
    )
    (net (code "55") (name "unconnected-(U$1-GPIO6-PadP8)") (class "Default")
      (node (ref "U$1") (pin "P8") (pinfunction "GPIO6_P8") (pintype "bidirectional"))
    )
    (net (code "56") (name "unconnected-(U$1-GPIO7-PadP9)") (class "Default")
      (node (ref "U$1") (pin "P9") (pinfunction "GPIO7_P9") (pintype "bidirectional"))
    )
    (net (code "57") (name "unconnected-(U$1-GPIO8-PadP11)") (class "Default")
      (node (ref "U$1") (pin "P11") (pinfunction "GPIO8_P11") (pintype "bidirectional"))
    )
    (net (code "58") (name "unconnected-(U$1-GPIO15-PadP18)") (class "Default")
      (node (ref "U$1") (pin "P18") (pinfunction "GPIO15_P18") (pintype "bidirectional"))
    )
    (net (code "59") (name "unconnected-(U$1-GPIO16-PadP27)") (class "Default")
      (node (ref "U$1") (pin "P27") (pinfunction "GPIO16_P27") (pintype "bidirectional"))
    )
    (net (code "60") (name "unconnected-(U$1-GPIO17-PadP28)") (class "Default")
      (node (ref "U$1") (pin "P28") (pinfunction "GPIO17_P28") (pintype "bidirectional"))
    )
    (net (code "61") (name "unconnected-(U$1-GPIO18-PadP29)") (class "Default")
      (node (ref "U$1") (pin "P29") (pinfunction "GPIO18_P29") (pintype "bidirectional"))
    )
    (net (code "62") (name "unconnected-(U$1-GPIO19-PadP30)") (class "Default")
      (node (ref "U$1") (pin "P30") (pinfunction "GPIO19_P30") (pintype "bidirectional"))
    )
    (net (code "63") (name "unconnected-(U$1-GPIO20-PadP31)") (class "Default")
      (node (ref "U$1") (pin "P31") (pinfunction "GPIO20_P31") (pintype "bidirectional"))
    )
    (net (code "64") (name "unconnected-(U$1-GPIO21-PadP32)") (class "Default")
      (node (ref "U$1") (pin "P32") (pinfunction "GPIO21_P32") (pintype "bidirectional"))
    )
    (net (code "65") (name "unconnected-(U$1-GPIO22-PadP34)") (class "Default")
      (node (ref "U$1") (pin "P34") (pinfunction "GPIO22_P34") (pintype "bidirectional"))
    )
    (net (code "66") (name "unconnected-(U$1-GPIO23-PadP35)") (class "Default")
      (node (ref "U$1") (pin "P35") (pinfunction "GPIO23_P35") (pintype "bidirectional"))
    )
    (net (code "67") (name "unconnected-(U$1-GPIO24-PadP36)") (class "Default")
      (node (ref "U$1") (pin "P36") (pinfunction "GPIO24_P36") (pintype "bidirectional"))
    )
    (net (code "68") (name "unconnected-(U$1-GPIO25-PadP37)") (class "Default")
      (node (ref "U$1") (pin "P37") (pinfunction "GPIO25_P37") (pintype "bidirectional"))
    )
    (net (code "69") (name "unconnected-(U$1-SWCLK-PadP24)") (class "Default")
      (node (ref "U$1") (pin "P24") (pinfunction "SWCLK_P24") (pintype "bidirectional"))
    )
    (net (code "70") (name "unconnected-(U$1-SWDIO-PadP25)") (class "Default")
      (node (ref "U$1") (pin "P25") (pinfunction "SWDIO_P25") (pintype "bidirectional"))
    )
    (net (code "71") (name "unconnected-(U$2-DCC-PadA5)") (class "Default")
      (node (ref "U$2") (pin "A5") (pinfunction "DCC_A5") (pintype "bidirectional"))
    )
    (net (code "72") (name "unconnected-(U$2-P.0.17-PadF3)") (class "Default")
      (node (ref "U$2") (pin "F3") (pinfunction "P.0.17_F3") (pintype "bidirectional"))
    )
    (net (code "73") (name "unconnected-(U$2-P0.03{slash}AIN1-PadD6)") (class "Default")
      (node (ref "U$2") (pin "D6") (pinfunction "P0.03/AIN1_D6") (pintype "bidirectional"))
    )
    (net (code "74") (name "unconnected-(U$2-P0.04{slash}AIN2-PadE5)") (class "Default")
      (node (ref "U$2") (pin "E5") (pinfunction "P0.04/AIN2_E5") (pintype "bidirectional"))
    )
    (net (code "75") (name "unconnected-(U$2-P0.05{slash}AIN3-PadE6)") (class "Default")
      (node (ref "U$2") (pin "E6") (pinfunction "P0.05/AIN3_E6") (pintype "bidirectional"))
    )
    (net (code "76") (name "unconnected-(U$2-P0.08-PadF6)") (class "Default")
      (node (ref "U$2") (pin "F6") (pinfunction "P0.08_F6") (pintype "bidirectional"))
    )
    (net (code "77") (name "unconnected-(U$2-P0.11-PadF5)") (class "Default")
      (node (ref "U$2") (pin "F5") (pinfunction "P0.11_F5") (pintype "bidirectional"))
    )
    (net (code "78") (name "unconnected-(U$2-P0.14-PadF4)") (class "Default")
      (node (ref "U$2") (pin "F4") (pinfunction "P0.14_F4") (pintype "bidirectional"))
    )
    (net (code "79") (name "unconnected-(U$2-P0.18-PadE2)") (class "Default")
      (node (ref "U$2") (pin "E2") (pinfunction "P0.18_E2") (pintype "bidirectional"))
    )
    (net (code "80") (name "unconnected-(U$2-XTL1_32KHZ{slash}P0.00-PadB5)") (class "Default")
      (node (ref "U$2") (pin "B5") (pinfunction "XTL1_32KHZ/P0.00_B5") (pintype "bidirectional"))
    )
    (net (code "81") (name "unconnected-(U$2-XTL2_32KHZ{slash}P0.01-PadD5)") (class "Default")
      (node (ref "U$2") (pin "D5") (pinfunction "XTL2_32KHZ/P0.01_D5") (pintype "bidirectional"))
    )
    (net (code "82") (name "unconnected-(U2-NC-Pad4)") (class "Default")
      (node (ref "U2") (pin "4") (pinfunction "NC_4") (pintype "no_connect"))
    )
  )
)
